# hw6.net
KiCad netlist of a schematic drawn in EAGLE
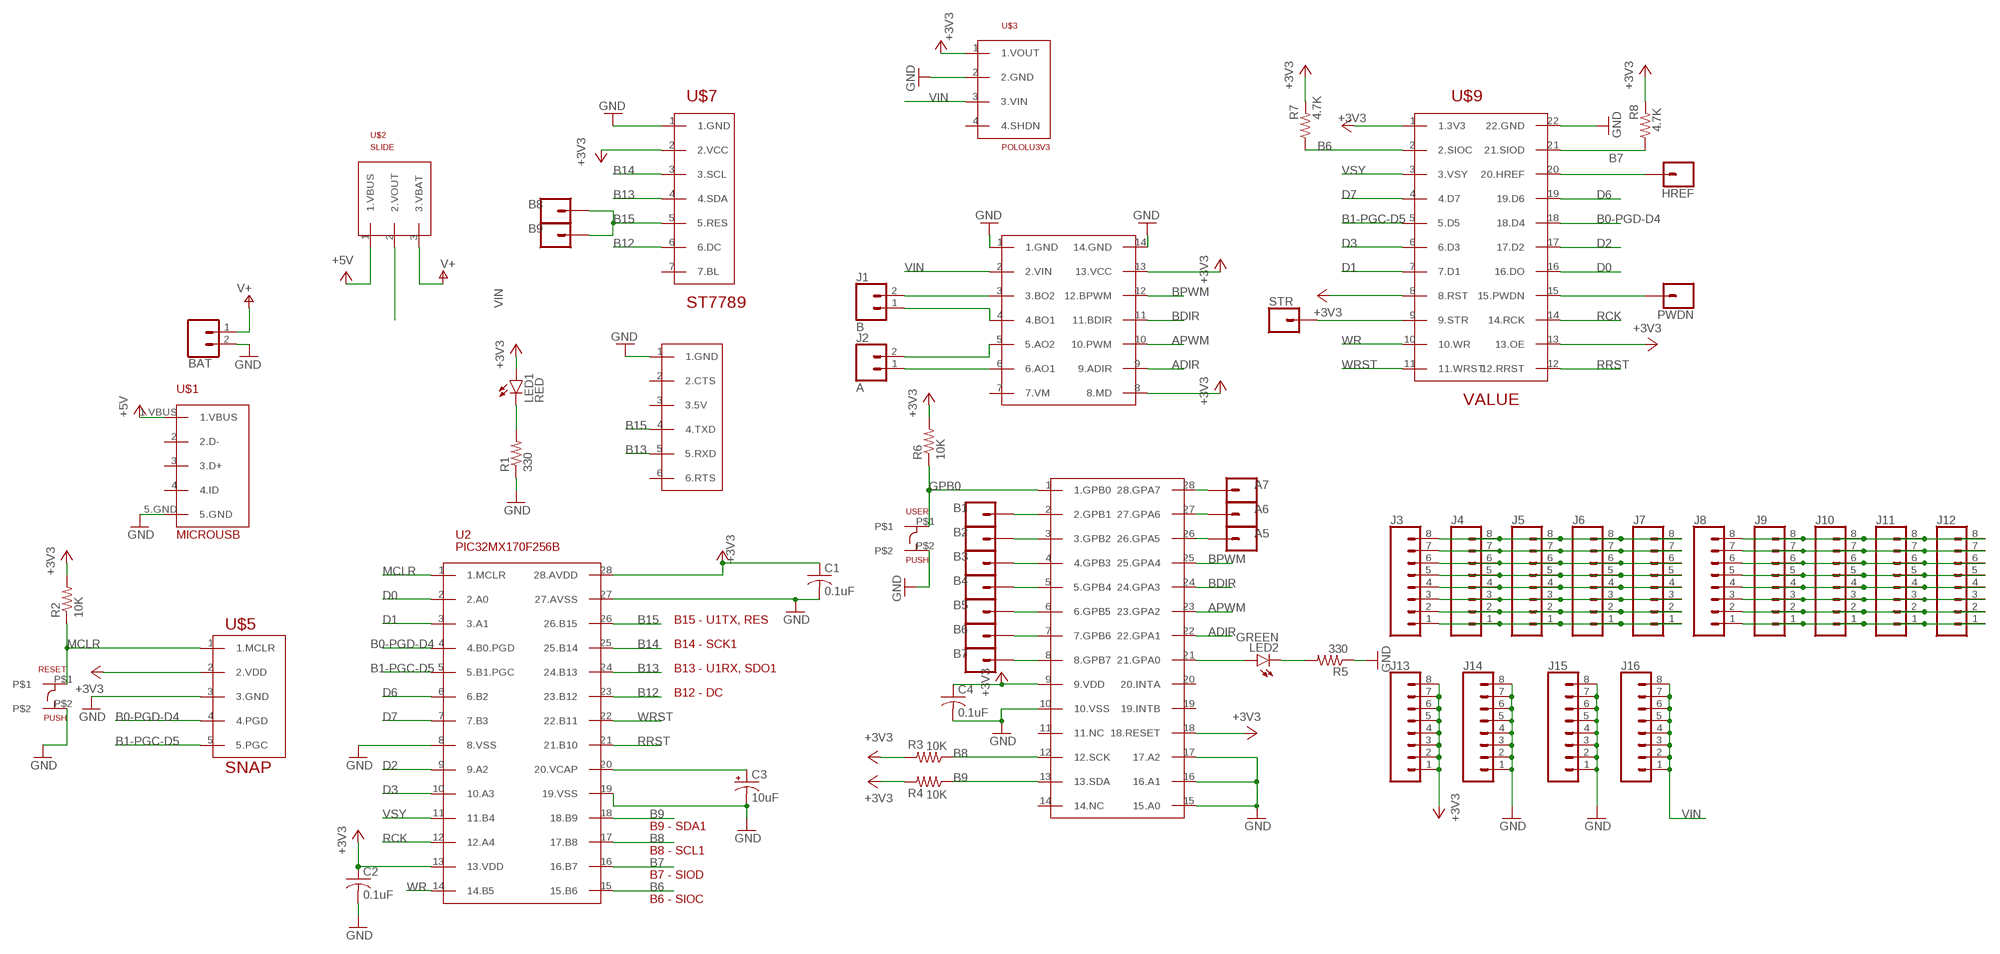
[diagram p0: schematic, sheet 1]

(export (version "E")
  (design (tool "Eeschema 10.0.6"))
  (components
    (comp (ref "A5")
      (value "CONN_01")
      (footprint "eagle-import:1X01")
      (libsource (lib "eagle-import") (part "CONN_01"))
    )
    (comp (ref "A6")
      (value "CONN_01")
      (footprint "eagle-import:1X01")
      (libsource (lib "eagle-import") (part "CONN_01"))
    )
    (comp (ref "A7")
      (value "CONN_01")
      (footprint "eagle-import:1X01")
      (libsource (lib "eagle-import") (part "CONN_01"))
    )
    (comp (ref "B1")
      (value "CONN_01")
      (footprint "eagle-import:1X01")
      (libsource (lib "eagle-import") (part "CONN_01"))
    )
    (comp (ref "B2")
      (value "CONN_01")
      (footprint "eagle-import:1X01")
      (libsource (lib "eagle-import") (part "CONN_01"))
    )
    (comp (ref "B3")
      (value "CONN_01")
      (footprint "eagle-import:1X01")
      (libsource (lib "eagle-import") (part "CONN_01"))
    )
    (comp (ref "B4")
      (value "CONN_01")
      (footprint "eagle-import:1X01")
      (libsource (lib "eagle-import") (part "CONN_01"))
    )
    (comp (ref "B5")
      (value "CONN_01")
      (footprint "eagle-import:1X01")
      (libsource (lib "eagle-import") (part "CONN_01"))
    )
    (comp (ref "B6")
      (value "CONN_01")
      (footprint "eagle-import:1X01")
      (libsource (lib "eagle-import") (part "CONN_01"))
    )
    (comp (ref "B7")
      (value "CONN_01")
      (footprint "eagle-import:1X01")
      (libsource (lib "eagle-import") (part "CONN_01"))
    )
    (comp (ref "B8")
      (value "CONN_01")
      (footprint "eagle-import:1X01")
      (libsource (lib "eagle-import") (part "CONN_01"))
    )
    (comp (ref "B9")
      (value "CONN_01")
      (footprint "eagle-import:1X01")
      (libsource (lib "eagle-import") (part "CONN_01"))
    )
    (comp (ref "BAT")
      (value "CONN_02")
      (footprint "eagle-import:1X02")
      (libsource (lib "eagle-import") (part "CONN_02"))
    )
    (comp (ref "C1")
      (value "0.1uF")
      (footprint "eagle-import:C025-030X050")
      (libsource (lib "eagle-import") (part "C-US025-030X050"))
    )
    (comp (ref "C2")
      (value "0.1uF")
      (footprint "eagle-import:C025-030X050")
      (libsource (lib "eagle-import") (part "C-US025-030X050"))
    )
    (comp (ref "C3")
      (value "10uF")
      (footprint "eagle-import:B45181B")
      (libsource (lib "eagle-import") (part "CPOL-USB45181B"))
    )
    (comp (ref "C4")
      (value "0.1uF")
      (footprint "eagle-import:C025-030X050")
      (libsource (lib "eagle-import") (part "C-US025-030X050"))
    )
    (comp (ref "HREF")
      (value "CONN_01")
      (footprint "eagle-import:1X01")
      (libsource (lib "eagle-import") (part "CONN_01"))
    )
    (comp (ref "J1")
      (value "B")
      (footprint "eagle-import:1X02")
      (libsource (lib "eagle-import") (part "CONN_02"))
    )
    (comp (ref "J2")
      (value "A")
      (footprint "eagle-import:1X02")
      (libsource (lib "eagle-import") (part "CONN_02"))
    )
    (comp (ref "J3")
      (value "CONN_08\"")
      (footprint "eagle-import:1X08")
      (libsource (lib "eagle-import") (part "CONN_08{dblquote}"))
    )
    (comp (ref "J4")
      (value "CONN_08\"")
      (footprint "eagle-import:1X08")
      (libsource (lib "eagle-import") (part "CONN_08{dblquote}"))
    )
    (comp (ref "J5")
      (value "CONN_08\"")
      (footprint "eagle-import:1X08")
      (libsource (lib "eagle-import") (part "CONN_08{dblquote}"))
    )
    (comp (ref "J6")
      (value "CONN_08\"")
      (footprint "eagle-import:1X08")
      (libsource (lib "eagle-import") (part "CONN_08{dblquote}"))
    )
    (comp (ref "J7")
      (value "CONN_08\"")
      (footprint "eagle-import:1X08")
      (libsource (lib "eagle-import") (part "CONN_08{dblquote}"))
    )
    (comp (ref "J8")
      (value "CONN_08\"")
      (footprint "eagle-import:1X08")
      (libsource (lib "eagle-import") (part "CONN_08{dblquote}"))
    )
    (comp (ref "J9")
      (value "CONN_08\"")
      (footprint "eagle-import:1X08")
      (libsource (lib "eagle-import") (part "CONN_08{dblquote}"))
    )
    (comp (ref "J10")
      (value "CONN_08\"")
      (footprint "eagle-import:1X08")
      (libsource (lib "eagle-import") (part "CONN_08{dblquote}"))
    )
    (comp (ref "J11")
      (value "CONN_08\"")
      (footprint "eagle-import:1X08")
      (libsource (lib "eagle-import") (part "CONN_08{dblquote}"))
    )
    (comp (ref "J12")
      (value "CONN_08\"")
      (footprint "eagle-import:1X08")
      (libsource (lib "eagle-import") (part "CONN_08{dblquote}"))
    )
    (comp (ref "J13")
      (value "CONN_08\"")
      (footprint "eagle-import:1X08")
      (libsource (lib "eagle-import") (part "CONN_08{dblquote}"))
    )
    (comp (ref "J14")
      (value "CONN_08\"")
      (footprint "eagle-import:1X08")
      (libsource (lib "eagle-import") (part "CONN_08{dblquote}"))
    )
    (comp (ref "J15")
      (value "CONN_08\"")
      (footprint "eagle-import:1X08")
      (libsource (lib "eagle-import") (part "CONN_08{dblquote}"))
    )
    (comp (ref "J16")
      (value "CONN_08\"")
      (footprint "eagle-import:1X08")
      (libsource (lib "eagle-import") (part "CONN_08{dblquote}"))
    )
    (comp (ref "LED1")
      (value "RED")
      (footprint "eagle-import:LED3MM")
      (libsource (lib "eagle-import") (part "LED3MM"))
    )
    (comp (ref "LED2")
      (value "GREEN")
      (footprint "eagle-import:LED3MM")
      (libsource (lib "eagle-import") (part "LED3MM"))
    )
    (comp (ref "PWDN")
      (value "CONN_01")
      (footprint "eagle-import:1X01")
      (libsource (lib "eagle-import") (part "CONN_01"))
    )
    (comp (ref "R1")
      (value "330")
      (footprint "eagle-import:0207_10")
      (libsource (lib "eagle-import") (part "R-US_0207/10"))
    )
    (comp (ref "R2")
      (value "10K")
      (footprint "eagle-import:0207_10")
      (libsource (lib "eagle-import") (part "R-US_0207/10"))
    )
    (comp (ref "R3")
      (value "10K")
      (footprint "eagle-import:0207_10")
      (libsource (lib "eagle-import") (part "R-US_0207/10"))
    )
    (comp (ref "R4")
      (value "10K")
      (footprint "eagle-import:0207_10")
      (libsource (lib "eagle-import") (part "R-US_0207/10"))
    )
    (comp (ref "R5")
      (value "330")
      (footprint "eagle-import:0207_10")
      (libsource (lib "eagle-import") (part "R-US_0207/10"))
    )
    (comp (ref "R6")
      (value "10K")
      (footprint "eagle-import:0207_10")
      (libsource (lib "eagle-import") (part "R-US_0207/10"))
    )
    (comp (ref "R7")
      (value "4.7K")
      (footprint "eagle-import:0207_10")
      (libsource (lib "eagle-import") (part "R-US_0207/10"))
    )
    (comp (ref "R8")
      (value "4.7K")
      (footprint "eagle-import:0207_10")
      (libsource (lib "eagle-import") (part "R-US_0207/10"))
    )
    (comp (ref "RESET")
      (value "PUSH")
      (footprint "eagle-import:PUSH")
      (libsource (lib "eagle-import") (part "PUSH"))
    )
    (comp (ref "STR")
      (value "CONN_01")
      (footprint "eagle-import:1X01")
      (libsource (lib "eagle-import") (part "CONN_01"))
    )
    (comp (ref "U$1")
      (value "MICROUSB")
      (footprint "eagle-import:MICROUSB")
      (libsource (lib "eagle-import") (part "MICROUSB"))
    )
    (comp (ref "U$2")
      (value "SLIDE")
      (footprint "eagle-import:SLIDE")
      (libsource (lib "eagle-import") (part "SLIDE"))
    )
    (comp (ref "U$3")
      (value "POLOLU3V3")
      (footprint "eagle-import:POLOLU3V3")
      (libsource (lib "eagle-import") (part "POLOLU3V3"))
    )
    (comp (ref "U$4")
      (value "DRV8835")
      (footprint "eagle-import:DRV8835")
      (libsource (lib "eagle-import") (part "DRV8835"))
    )
    (comp (ref "U$5")
      (value "SNAP")
      (footprint "eagle-import:SNAP")
      (libsource (lib "eagle-import") (part "SNAP"))
    )
    (comp (ref "U$6")
      (value "CP2104_FRIEND")
      (footprint "eagle-import:CP2104_FRIEND")
      (libsource (lib "eagle-import") (part "CP2104_FRIEND"))
    )
    (comp (ref "U$7")
      (value "ST7789")
      (footprint "eagle-import:ST7789")
      (libsource (lib "eagle-import") (part "ST7789"))
    )
    (comp (ref "U$8")
      (value "MCP23017")
      (footprint "eagle-import:DIL28-3")
      (libsource (lib "eagle-import") (part "MCP23017"))
    )
    (comp (ref "U$9")
      (value "OV7670FIFO")
      (footprint "eagle-import:OV7670FIFO")
      (libsource (lib "eagle-import") (part "OV7670FIFO"))
    )
    (comp (ref "U2")
      (value "PIC32MX170F256B")
      (footprint "eagle-import:DIL28-3")
      (libsource (lib "eagle-import") (part "PIC32MX170F256B"))
    )
    (comp (ref "USER")
      (value "PUSH")
      (footprint "eagle-import:PUSH")
      (libsource (lib "eagle-import") (part "PUSH"))
    )
  )
  (nets
    (net (code "1") (name "+3V3") (class "Default")
      (node (ref "C1") (pin "1") (pinfunction "1_1") (pintype "passive"))
      (node (ref "C2") (pin "1") (pinfunction "1_1") (pintype "passive"))
      (node (ref "C4") (pin "1") (pinfunction "1_1") (pintype "passive"))
      (node (ref "J13") (pin "1") (pinfunction "1_1") (pintype "passive"))
      (node (ref "J13") (pin "2") (pinfunction "2_2") (pintype "passive"))
      (node (ref "J13") (pin "3") (pinfunction "3_3") (pintype "passive"))
      (node (ref "J13") (pin "4") (pinfunction "4_4") (pintype "passive"))
      (node (ref "J13") (pin "5") (pinfunction "5_5") (pintype "passive"))
      (node (ref "J13") (pin "6") (pinfunction "6_6") (pintype "passive"))
      (node (ref "J13") (pin "7") (pinfunction "7_7") (pintype "passive"))
      (node (ref "J13") (pin "8") (pinfunction "8_8") (pintype "passive"))
      (node (ref "LED1") (pin "A") (pinfunction "A_A") (pintype "passive"))
      (node (ref "R2") (pin "2") (pinfunction "2_2") (pintype "passive"))
      (node (ref "R3") (pin "2") (pinfunction "2_2") (pintype "passive"))
      (node (ref "R4") (pin "2") (pinfunction "2_2") (pintype "passive"))
      (node (ref "R6") (pin "2") (pinfunction "2_2") (pintype "passive"))
      (node (ref "R7") (pin "2") (pinfunction "2_2") (pintype "passive"))
      (node (ref "R8") (pin "2") (pinfunction "2_2") (pintype "passive"))
      (node (ref "U$3") (pin "1") (pinfunction "1.VOUT_1") (pintype "bidirectional"))
      (node (ref "U$4") (pin "13") (pinfunction "13.VCC_13") (pintype "bidirectional"))
      (node (ref "U$4") (pin "8") (pinfunction "8.MD_8") (pintype "bidirectional"))
      (node (ref "U$5") (pin "2") (pinfunction "2.VDD_2") (pintype "bidirectional"))
      (node (ref "U$7") (pin "2") (pinfunction "2.VCC_2") (pintype "bidirectional"))
      (node (ref "U$8") (pin "18") (pinfunction "18.RESET_18") (pintype "bidirectional"))
      (node (ref "U$8") (pin "9") (pinfunction "9.VDD_9") (pintype "bidirectional"))
      (node (ref "U$9") (pin "1") (pinfunction "1.3V3_1") (pintype "bidirectional"))
      (node (ref "U$9") (pin "13") (pinfunction "13.OE_13") (pintype "bidirectional"))
      (node (ref "U$9") (pin "8") (pinfunction "8.RST_8") (pintype "bidirectional"))
      (node (ref "U2") (pin "13") (pinfunction "13.VDD_13") (pintype "bidirectional"))
      (node (ref "U2") (pin "28") (pinfunction "28.AVDD_28") (pintype "bidirectional"))
    )
    (net (code "2") (name "+5V") (class "Default")
      (node (ref "U$1") (pin "1.VBUS") (pinfunction "1.VBUS_1.VBUS") (pintype "bidirectional"))
      (node (ref "U$2") (pin "1") (pinfunction "1.VBUS_1") (pintype "bidirectional"))
    )
    (net (code "3") (name "/ADIR") (class "Default")
      (node (ref "U$4") (pin "9") (pinfunction "9.ADIR_9") (pintype "bidirectional"))
      (node (ref "U$8") (pin "22") (pinfunction "22.GPA1_22") (pintype "bidirectional"))
    )
    (net (code "4") (name "/APWM") (class "Default")
      (node (ref "U$4") (pin "10") (pinfunction "10.PWM_10") (pintype "bidirectional"))
      (node (ref "U$8") (pin "23") (pinfunction "23.GPA2_23") (pintype "bidirectional"))
    )
    (net (code "5") (name "/B0-PGD-D4") (class "Default")
      (node (ref "U$5") (pin "4") (pinfunction "4.PGD_4") (pintype "bidirectional"))
      (node (ref "U$9") (pin "18") (pinfunction "18.D4_18") (pintype "bidirectional"))
      (node (ref "U2") (pin "4") (pinfunction "4.B0.PGD_4") (pintype "bidirectional"))
    )
    (net (code "6") (name "/B1-PGC-D5") (class "Default")
      (node (ref "U$5") (pin "5") (pinfunction "5.PGC_5") (pintype "bidirectional"))
      (node (ref "U$9") (pin "5") (pinfunction "5.D5_5") (pintype "bidirectional"))
      (node (ref "U2") (pin "5") (pinfunction "5.B1.PGC_5") (pintype "bidirectional"))
    )
    (net (code "7") (name "/B6") (class "Default")
      (node (ref "R7") (pin "1") (pinfunction "1_1") (pintype "passive"))
      (node (ref "U$9") (pin "2") (pinfunction "2.SIOC_2") (pintype "bidirectional"))
      (node (ref "U2") (pin "15") (pinfunction "15.B6_15") (pintype "bidirectional"))
    )
    (net (code "8") (name "/B7") (class "Default")
      (node (ref "R8") (pin "1") (pinfunction "1_1") (pintype "passive"))
      (node (ref "U$9") (pin "21") (pinfunction "21.SIOD_21") (pintype "bidirectional"))
      (node (ref "U2") (pin "16") (pinfunction "16.B7_16") (pintype "bidirectional"))
    )
    (net (code "9") (name "/B8") (class "Default")
      (node (ref "R3") (pin "1") (pinfunction "1_1") (pintype "passive"))
      (node (ref "U$8") (pin "12") (pinfunction "12.SCK_12") (pintype "bidirectional"))
      (node (ref "U2") (pin "17") (pinfunction "17.B8_17") (pintype "bidirectional"))
    )
    (net (code "10") (name "/B9") (class "Default")
      (node (ref "R4") (pin "1") (pinfunction "1_1") (pintype "passive"))
      (node (ref "U$8") (pin "13") (pinfunction "13.SDA_13") (pintype "bidirectional"))
      (node (ref "U2") (pin "18") (pinfunction "18.B9_18") (pintype "bidirectional"))
    )
    (net (code "11") (name "/B12") (class "Default")
      (node (ref "U$7") (pin "6") (pinfunction "6.DC_6") (pintype "bidirectional"))
      (node (ref "U2") (pin "23") (pinfunction "23.B12_23") (pintype "bidirectional"))
    )
    (net (code "12") (name "/B13") (class "Default")
      (node (ref "U$6") (pin "5") (pinfunction "5.RXD_5") (pintype "bidirectional"))
      (node (ref "U$7") (pin "4") (pinfunction "4.SDA_4") (pintype "bidirectional"))
      (node (ref "U2") (pin "24") (pinfunction "24.B13_24") (pintype "bidirectional"))
    )
    (net (code "13") (name "/B14") (class "Default")
      (node (ref "U$7") (pin "3") (pinfunction "3.SCL_3") (pintype "bidirectional"))
      (node (ref "U2") (pin "25") (pinfunction "25.B14_25") (pintype "bidirectional"))
    )
    (net (code "14") (name "/B15") (class "Default")
      (node (ref "B8") (pin "1") (pinfunction "1_1") (pintype "passive"))
      (node (ref "B9") (pin "1") (pinfunction "1_1") (pintype "passive"))
      (node (ref "U$6") (pin "4") (pinfunction "4.TXD_4") (pintype "bidirectional"))
      (node (ref "U$7") (pin "5") (pinfunction "5.RES_5") (pintype "bidirectional"))
      (node (ref "U2") (pin "26") (pinfunction "26.B15_26") (pintype "bidirectional"))
    )
    (net (code "15") (name "/BDIR") (class "Default")
      (node (ref "U$4") (pin "11") (pinfunction "11.BDIR_11") (pintype "bidirectional"))
      (node (ref "U$8") (pin "24") (pinfunction "24.GPA3_24") (pintype "bidirectional"))
    )
    (net (code "16") (name "/BPWM") (class "Default")
      (node (ref "U$4") (pin "12") (pinfunction "12.BPWM_12") (pintype "bidirectional"))
      (node (ref "U$8") (pin "25") (pinfunction "25.GPA4_25") (pintype "bidirectional"))
    )
    (net (code "17") (name "/D0") (class "Default")
      (node (ref "U$9") (pin "16") (pinfunction "16.DO_16") (pintype "bidirectional"))
      (node (ref "U2") (pin "2") (pinfunction "2.A0_2") (pintype "bidirectional"))
    )
    (net (code "18") (name "/D1") (class "Default")
      (node (ref "U$9") (pin "7") (pinfunction "7.D1_7") (pintype "bidirectional"))
      (node (ref "U2") (pin "3") (pinfunction "3.A1_3") (pintype "bidirectional"))
    )
    (net (code "19") (name "/D2") (class "Default")
      (node (ref "U$9") (pin "17") (pinfunction "17.D2_17") (pintype "bidirectional"))
      (node (ref "U2") (pin "9") (pinfunction "9.A2_9") (pintype "bidirectional"))
    )
    (net (code "20") (name "/D3") (class "Default")
      (node (ref "U$9") (pin "6") (pinfunction "6.D3_6") (pintype "bidirectional"))
      (node (ref "U2") (pin "10") (pinfunction "10.A3_10") (pintype "bidirectional"))
    )
    (net (code "21") (name "/D6") (class "Default")
      (node (ref "U$9") (pin "19") (pinfunction "19.D6_19") (pintype "bidirectional"))
      (node (ref "U2") (pin "6") (pinfunction "6.B2_6") (pintype "bidirectional"))
    )
    (net (code "22") (name "/D7") (class "Default")
      (node (ref "U$9") (pin "4") (pinfunction "4.D7_4") (pintype "bidirectional"))
      (node (ref "U2") (pin "7") (pinfunction "7.B3_7") (pintype "bidirectional"))
    )
    (net (code "23") (name "/GPB0") (class "Default")
      (node (ref "R6") (pin "1") (pinfunction "1_1") (pintype "passive"))
      (node (ref "U$8") (pin "1") (pinfunction "1.GPB0_1") (pintype "bidirectional"))
      (node (ref "USER") (pin "P$1") (pinfunction "P$1_P$1") (pintype "bidirectional"))
    )
    (net (code "24") (name "/MCLR") (class "Default")
      (node (ref "R2") (pin "1") (pinfunction "1_1") (pintype "passive"))
      (node (ref "RESET") (pin "P$1") (pinfunction "P$1_P$1") (pintype "bidirectional"))
      (node (ref "U$5") (pin "1") (pinfunction "1.MCLR_1") (pintype "bidirectional"))
      (node (ref "U2") (pin "1") (pinfunction "1.MCLR_1") (pintype "bidirectional"))
    )
    (net (code "25") (name "/RCK") (class "Default")
      (node (ref "U$9") (pin "14") (pinfunction "14.RCK_14") (pintype "bidirectional"))
      (node (ref "U2") (pin "12") (pinfunction "12.A4_12") (pintype "bidirectional"))
    )
    (net (code "26") (name "/RRST") (class "Default")
      (node (ref "U$9") (pin "12") (pinfunction "12.RRST_12") (pintype "bidirectional"))
      (node (ref "U2") (pin "21") (pinfunction "21.B10_21") (pintype "bidirectional"))
    )
    (net (code "27") (name "/VIN") (class "Default")
      (node (ref "J16") (pin "1") (pinfunction "1_1") (pintype "passive"))
      (node (ref "J16") (pin "2") (pinfunction "2_2") (pintype "passive"))
      (node (ref "J16") (pin "3") (pinfunction "3_3") (pintype "passive"))
      (node (ref "J16") (pin "4") (pinfunction "4_4") (pintype "passive"))
      (node (ref "J16") (pin "5") (pinfunction "5_5") (pintype "passive"))
      (node (ref "J16") (pin "6") (pinfunction "6_6") (pintype "passive"))
      (node (ref "J16") (pin "7") (pinfunction "7_7") (pintype "passive"))
      (node (ref "J16") (pin "8") (pinfunction "8_8") (pintype "passive"))
      (node (ref "U$2") (pin "2") (pinfunction "2.VOUT_2") (pintype "bidirectional"))
      (node (ref "U$3") (pin "3") (pinfunction "3.VIN_3") (pintype "bidirectional"))
      (node (ref "U$4") (pin "2") (pinfunction "2.VIN_2") (pintype "bidirectional"))
    )
    (net (code "28") (name "/VSY") (class "Default")
      (node (ref "U$9") (pin "3") (pinfunction "3.VSY_3") (pintype "bidirectional"))
      (node (ref "U2") (pin "11") (pinfunction "11.B4_11") (pintype "bidirectional"))
    )
    (net (code "29") (name "/WR") (class "Default")
      (node (ref "U$9") (pin "10") (pinfunction "10.WR_10") (pintype "bidirectional"))
      (node (ref "U2") (pin "14") (pinfunction "14.B5_14") (pintype "bidirectional"))
    )
    (net (code "30") (name "/WRST") (class "Default")
      (node (ref "U$9") (pin "11") (pinfunction "11.WRST_11") (pintype "bidirectional"))
      (node (ref "U2") (pin "22") (pinfunction "22.B11_22") (pintype "bidirectional"))
    )
    (net (code "31") (name "GND") (class "Default")
      (node (ref "BAT") (pin "2") (pinfunction "2_2") (pintype "passive"))
      (node (ref "C1") (pin "2") (pinfunction "2_2") (pintype "passive"))
      (node (ref "C2") (pin "2") (pinfunction "2_2") (pintype "passive"))
      (node (ref "C3") (pin "-") (pinfunction "-_-") (pintype "passive"))
      (node (ref "C4") (pin "2") (pinfunction "2_2") (pintype "passive"))
      (node (ref "J14") (pin "1") (pinfunction "1_1") (pintype "passive"))
      (node (ref "J14") (pin "2") (pinfunction "2_2") (pintype "passive"))
      (node (ref "J14") (pin "3") (pinfunction "3_3") (pintype "passive"))
      (node (ref "J14") (pin "4") (pinfunction "4_4") (pintype "passive"))
      (node (ref "J14") (pin "5") (pinfunction "5_5") (pintype "passive"))
      (node (ref "J14") (pin "6") (pinfunction "6_6") (pintype "passive"))
      (node (ref "J14") (pin "7") (pinfunction "7_7") (pintype "passive"))
      (node (ref "J14") (pin "8") (pinfunction "8_8") (pintype "passive"))
      (node (ref "J15") (pin "1") (pinfunction "1_1") (pintype "passive"))
      (node (ref "J15") (pin "2") (pinfunction "2_2") (pintype "passive"))
      (node (ref "J15") (pin "3") (pinfunction "3_3") (pintype "passive"))
      (node (ref "J15") (pin "4") (pinfunction "4_4") (pintype "passive"))
      (node (ref "J15") (pin "5") (pinfunction "5_5") (pintype "passive"))
      (node (ref "J15") (pin "6") (pinfunction "6_6") (pintype "passive"))
      (node (ref "J15") (pin "7") (pinfunction "7_7") (pintype "passive"))
      (node (ref "J15") (pin "8") (pinfunction "8_8") (pintype "passive"))
      (node (ref "R1") (pin "1") (pinfunction "1_1") (pintype "passive"))
      (node (ref "R5") (pin "1") (pinfunction "1_1") (pintype "passive"))
      (node (ref "RESET") (pin "P$2") (pinfunction "P$2_P$2") (pintype "bidirectional"))
      (node (ref "U$1") (pin "5.GND") (pinfunction "5.GND_5.GND") (pintype "bidirectional"))
      (node (ref "U$3") (pin "2") (pinfunction "2.GND_2") (pintype "bidirectional"))
      (node (ref "U$4") (pin "1") (pinfunction "1.GND_1") (pintype "bidirectional"))
      (node (ref "U$4") (pin "14") (pinfunction "14.GND_14") (pintype "bidirectional"))
      (node (ref "U$5") (pin "3") (pinfunction "3.GND_3") (pintype "bidirectional"))
      (node (ref "U$6") (pin "1") (pinfunction "1.GND_1") (pintype "bidirectional"))
      (node (ref "U$7") (pin "1") (pinfunction "1.GND_1") (pintype "bidirectional"))
      (node (ref "U$8") (pin "10") (pinfunction "10.VSS_10") (pintype "bidirectional"))
      (node (ref "U$8") (pin "15") (pinfunction "15.A0_15") (pintype "bidirectional"))
      (node (ref "U$8") (pin "16") (pinfunction "16.A1_16") (pintype "bidirectional"))
      (node (ref "U$8") (pin "17") (pinfunction "17.A2_17") (pintype "bidirectional"))
      (node (ref "U$9") (pin "22") (pinfunction "22.GND_22") (pintype "bidirectional"))
      (node (ref "U2") (pin "19") (pinfunction "19.VSS_19") (pintype "bidirectional"))
      (node (ref "U2") (pin "27") (pinfunction "27.AVSS_27") (pintype "bidirectional"))
      (node (ref "U2") (pin "8") (pinfunction "8.VSS_8") (pintype "bidirectional"))
      (node (ref "USER") (pin "P$2") (pinfunction "P$2_P$2") (pintype "bidirectional"))
    )
    (net (code "32") (name "Net-(J3-Pad1)") (class "Default")
      (node (ref "J3") (pin "1") (pinfunction "1_1") (pintype "passive"))
      (node (ref "J4") (pin "1") (pinfunction "1_1") (pintype "passive"))
      (node (ref "J5") (pin "1") (pinfunction "1_1") (pintype "passive"))
      (node (ref "J6") (pin "1") (pinfunction "1_1") (pintype "passive"))
      (node (ref "J7") (pin "1") (pinfunction "1_1") (pintype "passive"))
    )
    (net (code "33") (name "Net-(J3-Pad2)") (class "Default")
      (node (ref "J3") (pin "2") (pinfunction "2_2") (pintype "passive"))
      (node (ref "J4") (pin "2") (pinfunction "2_2") (pintype "passive"))
      (node (ref "J5") (pin "2") (pinfunction "2_2") (pintype "passive"))
      (node (ref "J6") (pin "2") (pinfunction "2_2") (pintype "passive"))
      (node (ref "J7") (pin "2") (pinfunction "2_2") (pintype "passive"))
    )
    (net (code "34") (name "Net-(J3-Pad3)") (class "Default")
      (node (ref "J3") (pin "3") (pinfunction "3_3") (pintype "passive"))
      (node (ref "J4") (pin "3") (pinfunction "3_3") (pintype "passive"))
      (node (ref "J5") (pin "3") (pinfunction "3_3") (pintype "passive"))
      (node (ref "J6") (pin "3") (pinfunction "3_3") (pintype "passive"))
      (node (ref "J7") (pin "3") (pinfunction "3_3") (pintype "passive"))
    )
    (net (code "35") (name "Net-(J3-Pad4)") (class "Default")
      (node (ref "J3") (pin "4") (pinfunction "4_4") (pintype "passive"))
      (node (ref "J4") (pin "4") (pinfunction "4_4") (pintype "passive"))
      (node (ref "J5") (pin "4") (pinfunction "4_4") (pintype "passive"))
      (node (ref "J6") (pin "4") (pinfunction "4_4") (pintype "passive"))
      (node (ref "J7") (pin "4") (pinfunction "4_4") (pintype "passive"))
    )
    (net (code "36") (name "Net-(J3-Pad5)") (class "Default")
      (node (ref "J3") (pin "5") (pinfunction "5_5") (pintype "passive"))
      (node (ref "J4") (pin "5") (pinfunction "5_5") (pintype "passive"))
      (node (ref "J5") (pin "5") (pinfunction "5_5") (pintype "passive"))
      (node (ref "J6") (pin "5") (pinfunction "5_5") (pintype "passive"))
      (node (ref "J7") (pin "5") (pinfunction "5_5") (pintype "passive"))
    )
    (net (code "37") (name "Net-(J3-Pad6)") (class "Default")
      (node (ref "J3") (pin "6") (pinfunction "6_6") (pintype "passive"))
      (node (ref "J4") (pin "6") (pinfunction "6_6") (pintype "passive"))
      (node (ref "J5") (pin "6") (pinfunction "6_6") (pintype "passive"))
      (node (ref "J6") (pin "6") (pinfunction "6_6") (pintype "passive"))
      (node (ref "J7") (pin "6") (pinfunction "6_6") (pintype "passive"))
    )
    (net (code "38") (name "Net-(J3-Pad7)") (class "Default")
      (node (ref "J3") (pin "7") (pinfunction "7_7") (pintype "passive"))
      (node (ref "J4") (pin "7") (pinfunction "7_7") (pintype "passive"))
      (node (ref "J5") (pin "7") (pinfunction "7_7") (pintype "passive"))
      (node (ref "J6") (pin "7") (pinfunction "7_7") (pintype "passive"))
      (node (ref "J7") (pin "7") (pinfunction "7_7") (pintype "passive"))
    )
    (net (code "39") (name "Net-(J3-Pad8)") (class "Default")
      (node (ref "J3") (pin "8") (pinfunction "8_8") (pintype "passive"))
      (node (ref "J4") (pin "8") (pinfunction "8_8") (pintype "passive"))
      (node (ref "J5") (pin "8") (pinfunction "8_8") (pintype "passive"))
      (node (ref "J6") (pin "8") (pinfunction "8_8") (pintype "passive"))
      (node (ref "J7") (pin "8") (pinfunction "8_8") (pintype "passive"))
    )
    (net (code "40") (name "Net-(J10-Pad1)") (class "Default")
      (node (ref "J10") (pin "1") (pinfunction "1_1") (pintype "passive"))
      (node (ref "J11") (pin "1") (pinfunction "1_1") (pintype "passive"))
      (node (ref "J12") (pin "1") (pinfunction "1_1") (pintype "passive"))
      (node (ref "J8") (pin "1") (pinfunction "1_1") (pintype "passive"))
      (node (ref "J9") (pin "1") (pinfunction "1_1") (pintype "passive"))
    )
    (net (code "41") (name "Net-(J10-Pad2)") (class "Default")
      (node (ref "J10") (pin "2") (pinfunction "2_2") (pintype "passive"))
      (node (ref "J11") (pin "2") (pinfunction "2_2") (pintype "passive"))
      (node (ref "J12") (pin "2") (pinfunction "2_2") (pintype "passive"))
      (node (ref "J8") (pin "2") (pinfunction "2_2") (pintype "passive"))
      (node (ref "J9") (pin "2") (pinfunction "2_2") (pintype "passive"))
    )
    (net (code "42") (name "Net-(J10-Pad3)") (class "Default")
      (node (ref "J10") (pin "3") (pinfunction "3_3") (pintype "passive"))
      (node (ref "J11") (pin "3") (pinfunction "3_3") (pintype "passive"))
      (node (ref "J12") (pin "3") (pinfunction "3_3") (pintype "passive"))
      (node (ref "J8") (pin "3") (pinfunction "3_3") (pintype "passive"))
      (node (ref "J9") (pin "3") (pinfunction "3_3") (pintype "passive"))
    )
    (net (code "43") (name "Net-(J10-Pad4)") (class "Default")
      (node (ref "J10") (pin "4") (pinfunction "4_4") (pintype "passive"))
      (node (ref "J11") (pin "4") (pinfunction "4_4") (pintype "passive"))
      (node (ref "J12") (pin "4") (pinfunction "4_4") (pintype "passive"))
      (node (ref "J8") (pin "4") (pinfunction "4_4") (pintype "passive"))
      (node (ref "J9") (pin "4") (pinfunction "4_4") (pintype "passive"))
    )
    (net (code "44") (name "Net-(J10-Pad5)") (class "Default")
      (node (ref "J10") (pin "5") (pinfunction "5_5") (pintype "passive"))
      (node (ref "J11") (pin "5") (pinfunction "5_5") (pintype "passive"))
      (node (ref "J12") (pin "5") (pinfunction "5_5") (pintype "passive"))
      (node (ref "J8") (pin "5") (pinfunction "5_5") (pintype "passive"))
      (node (ref "J9") (pin "5") (pinfunction "5_5") (pintype "passive"))
    )
    (net (code "45") (name "Net-(J10-Pad6)") (class "Default")
      (node (ref "J10") (pin "6") (pinfunction "6_6") (pintype "passive"))
      (node (ref "J11") (pin "6") (pinfunction "6_6") (pintype "passive"))
      (node (ref "J12") (pin "6") (pinfunction "6_6") (pintype "passive"))
      (node (ref "J8") (pin "6") (pinfunction "6_6") (pintype "passive"))
      (node (ref "J9") (pin "6") (pinfunction "6_6") (pintype "passive"))
    )
    (net (code "46") (name "Net-(J10-Pad7)") (class "Default")
      (node (ref "J10") (pin "7") (pinfunction "7_7") (pintype "passive"))
      (node (ref "J11") (pin "7") (pinfunction "7_7") (pintype "passive"))
      (node (ref "J12") (pin "7") (pinfunction "7_7") (pintype "passive"))
      (node (ref "J8") (pin "7") (pinfunction "7_7") (pintype "passive"))
      (node (ref "J9") (pin "7") (pinfunction "7_7") (pintype "passive"))
    )
    (net (code "47") (name "Net-(J10-Pad8)") (class "Default")
      (node (ref "J10") (pin "8") (pinfunction "8_8") (pintype "passive"))
      (node (ref "J11") (pin "8") (pinfunction "8_8") (pintype "passive"))
      (node (ref "J12") (pin "8") (pinfunction "8_8") (pintype "passive"))
      (node (ref "J8") (pin "8") (pinfunction "8_8") (pintype "passive"))
      (node (ref "J9") (pin "8") (pinfunction "8_8") (pintype "passive"))
    )
    (net (code "48") (name "Net-(LED1-C)") (class "Default")
      (node (ref "LED1") (pin "K") (pinfunction "C_K") (pintype "passive"))
      (node (ref "R1") (pin "2") (pinfunction "2_2") (pintype "passive"))
    )
    (net (code "49") (name "Net-(LED2-C)") (class "Default")
      (node (ref "LED2") (pin "K") (pinfunction "C_K") (pintype "passive"))
      (node (ref "R5") (pin "2") (pinfunction "2_2") (pintype "passive"))
    )
    (net (code "50") (name "Net-(U$4-3.BO2)") (class "Default")
      (node (ref "J1") (pin "2") (pinfunction "2_2") (pintype "passive"))
      (node (ref "U$4") (pin "3") (pinfunction "3.BO2_3") (pintype "bidirectional"))
    )
    (net (code "51") (name "Net-(U$4-4.BO1)") (class "Default")
      (node (ref "J1") (pin "1") (pinfunction "1_1") (pintype "passive"))
      (node (ref "U$4") (pin "4") (pinfunction "4.BO1_4") (pintype "bidirectional"))
    )
    (net (code "52") (name "Net-(U$4-5.AO2)") (class "Default")
      (node (ref "J2") (pin "2") (pinfunction "2_2") (pintype "passive"))
      (node (ref "U$4") (pin "5") (pinfunction "5.AO2_5") (pintype "bidirectional"))
    )
    (net (code "53") (name "Net-(U$4-6.AO1)") (class "Default")
      (node (ref "J2") (pin "1") (pinfunction "1_1") (pintype "passive"))
      (node (ref "U$4") (pin "6") (pinfunction "6.AO1_6") (pintype "bidirectional"))
    )
    (net (code "54") (name "Net-(U$8-2.GPB1)") (class "Default")
      (node (ref "B1") (pin "1") (pinfunction "1_1") (pintype "passive"))
      (node (ref "U$8") (pin "2") (pinfunction "2.GPB1_2") (pintype "bidirectional"))
    )
    (net (code "55") (name "Net-(U$8-3.GPB2)") (class "Default")
      (node (ref "B2") (pin "1") (pinfunction "1_1") (pintype "passive"))
      (node (ref "U$8") (pin "3") (pinfunction "3.GPB2_3") (pintype "bidirectional"))
    )
    (net (code "56") (name "Net-(U$8-4.GPB3)") (class "Default")
      (node (ref "B3") (pin "1") (pinfunction "1_1") (pintype "passive"))
      (node (ref "U$8") (pin "4") (pinfunction "4.GPB3_4") (pintype "bidirectional"))
    )
    (net (code "57") (name "Net-(U$8-5.GPB4)") (class "Default")
      (node (ref "B4") (pin "1") (pinfunction "1_1") (pintype "passive"))
      (node (ref "U$8") (pin "5") (pinfunction "5.GPB4_5") (pintype "bidirectional"))
    )
    (net (code "58") (name "Net-(U$8-6.GPB5)") (class "Default")
      (node (ref "B5") (pin "1") (pinfunction "1_1") (pintype "passive"))
      (node (ref "U$8") (pin "6") (pinfunction "6.GPB5_6") (pintype "bidirectional"))
    )
    (net (code "59") (name "Net-(U$8-7.GPB6)") (class "Default")
      (node (ref "B6") (pin "1") (pinfunction "1_1") (pintype "passive"))
      (node (ref "U$8") (pin "7") (pinfunction "7.GPB6_7") (pintype "bidirectional"))
    )
    (net (code "60") (name "Net-(U$8-8.GPB7)") (class "Default")
      (node (ref "B7") (pin "1") (pinfunction "1_1") (pintype "passive"))
      (node (ref "U$8") (pin "8") (pinfunction "8.GPB7_8") (pintype "bidirectional"))
    )
    (net (code "61") (name "Net-(U$8-21.GPA0)") (class "Default")
      (node (ref "LED2") (pin "A") (pinfunction "A_A") (pintype "passive"))
      (node (ref "U$8") (pin "21") (pinfunction "21.GPA0_21") (pintype "bidirectional"))
    )
    (net (code "62") (name "Net-(U$8-26.GPA5)") (class "Default")
      (node (ref "A5") (pin "1") (pinfunction "1_1") (pintype "passive"))
      (node (ref "U$8") (pin "26") (pinfunction "26.GPA5_26") (pintype "bidirectional"))
    )
    (net (code "63") (name "Net-(U$8-27.GPA6)") (class "Default")
      (node (ref "A6") (pin "1") (pinfunction "1_1") (pintype "passive"))
      (node (ref "U$8") (pin "27") (pinfunction "27.GPA6_27") (pintype "bidirectional"))
    )
    (net (code "64") (name "Net-(U$8-28.GPA7)") (class "Default")
      (node (ref "A7") (pin "1") (pinfunction "1_1") (pintype "passive"))
      (node (ref "U$8") (pin "28") (pinfunction "28.GPA7_28") (pintype "bidirectional"))
    )
    (net (code "65") (name "Net-(U$9-9.STR)") (class "Default")
      (node (ref "STR") (pin "1") (pinfunction "1_1") (pintype "passive"))
      (node (ref "U$9") (pin "9") (pinfunction "9.STR_9") (pintype "bidirectional"))
    )
    (net (code "66") (name "Net-(U$9-15.PWDN)") (class "Default")
      (node (ref "PWDN") (pin "1") (pinfunction "1_1") (pintype "passive"))
      (node (ref "U$9") (pin "15") (pinfunction "15.PWDN_15") (pintype "bidirectional"))
    )
    (net (code "67") (name "Net-(U$9-20.HREF)") (class "Default")
      (node (ref "HREF") (pin "1") (pinfunction "1_1") (pintype "passive"))
      (node (ref "U$9") (pin "20") (pinfunction "20.HREF_20") (pintype "bidirectional"))
    )
    (net (code "68") (name "Net-(U2-20.VCAP)") (class "Default")
      (node (ref "C3") (pin "+") (pinfunction "+_+") (pintype "passive"))
      (node (ref "U2") (pin "20") (pinfunction "20.VCAP_20") (pintype "bidirectional"))
    )
    (net (code "69") (name "V+") (class "Default")
      (node (ref "BAT") (pin "1") (pinfunction "1_1") (pintype "passive"))
      (node (ref "U$2") (pin "3") (pinfunction "3.VBAT_3") (pintype "bidirectional"))
    )
    (net (code "70") (name "unconnected-(U$1-2.D--Pad2)") (class "Default")
      (node (ref "U$1") (pin "2") (pinfunction "2.D-_2") (pintype "bidirectional"))
    )
    (net (code "71") (name "unconnected-(U$1-3.D+-Pad3)") (class "Default")
      (node (ref "U$1") (pin "3") (pinfunction "3.D+_3") (pintype "bidirectional"))
    )
    (net (code "72") (name "unconnected-(U$1-4.ID-Pad4)") (class "Default")
      (node (ref "U$1") (pin "4") (pinfunction "4.ID_4") (pintype "bidirectional"))
    )
    (net (code "73") (name "unconnected-(U$3-4.SHDN-Pad4)") (class "Default")
      (node (ref "U$3") (pin "4") (pinfunction "4.SHDN_4") (pintype "bidirectional"))
    )
    (net (code "74") (name "unconnected-(U$4-7.VM-Pad7)") (class "Default")
      (node (ref "U$4") (pin "7") (pinfunction "7.VM_7") (pintype "bidirectional"))
    )
    (net (code "75") (name "unconnected-(U$6-2.CTS-Pad2)") (class "Default")
      (node (ref "U$6") (pin "2") (pinfunction "2.CTS_2") (pintype "bidirectional"))
    )
    (net (code "76") (name "unconnected-(U$6-3.5V-Pad3)") (class "Default")
      (node (ref "U$6") (pin "3") (pinfunction "3.5V_3") (pintype "bidirectional"))
    )
    (net (code "77") (name "unconnected-(U$6-6.RTS-Pad6)") (class "Default")
      (node (ref "U$6") (pin "6") (pinfunction "6.RTS_6") (pintype "bidirectional"))
    )
    (net (code "78") (name "unconnected-(U$7-7.BL-Pad7)") (class "Default")
      (node (ref "U$7") (pin "7") (pinfunction "7.BL_7") (pintype "bidirectional"))
    )
    (net (code "79") (name "unconnected-(U$8-11.NC-Pad11)") (class "Default")
      (node (ref "U$8") (pin "11") (pinfunction "11.NC_11") (pintype "bidirectional"))
    )
    (net (code "80") (name "unconnected-(U$8-14.NC-Pad14)") (class "Default")
      (node (ref "U$8") (pin "14") (pinfunction "14.NC_14") (pintype "bidirectional"))
    )
    (net (code "81") (name "unconnected-(U$8-19.INTB-Pad19)") (class "Default")
      (node (ref "U$8") (pin "19") (pinfunction "19.INTB_19") (pintype "bidirectional"))
    )
    (net (code "82") (name "unconnected-(U$8-20.INTA-Pad20)") (class "Default")
      (node (ref "U$8") (pin "20") (pinfunction "20.INTA_20") (pintype "bidirectional"))
    )
  )
)
